# LED_Driver_-_4.net
KiCad netlist of a schematic drawn in Altium Designer
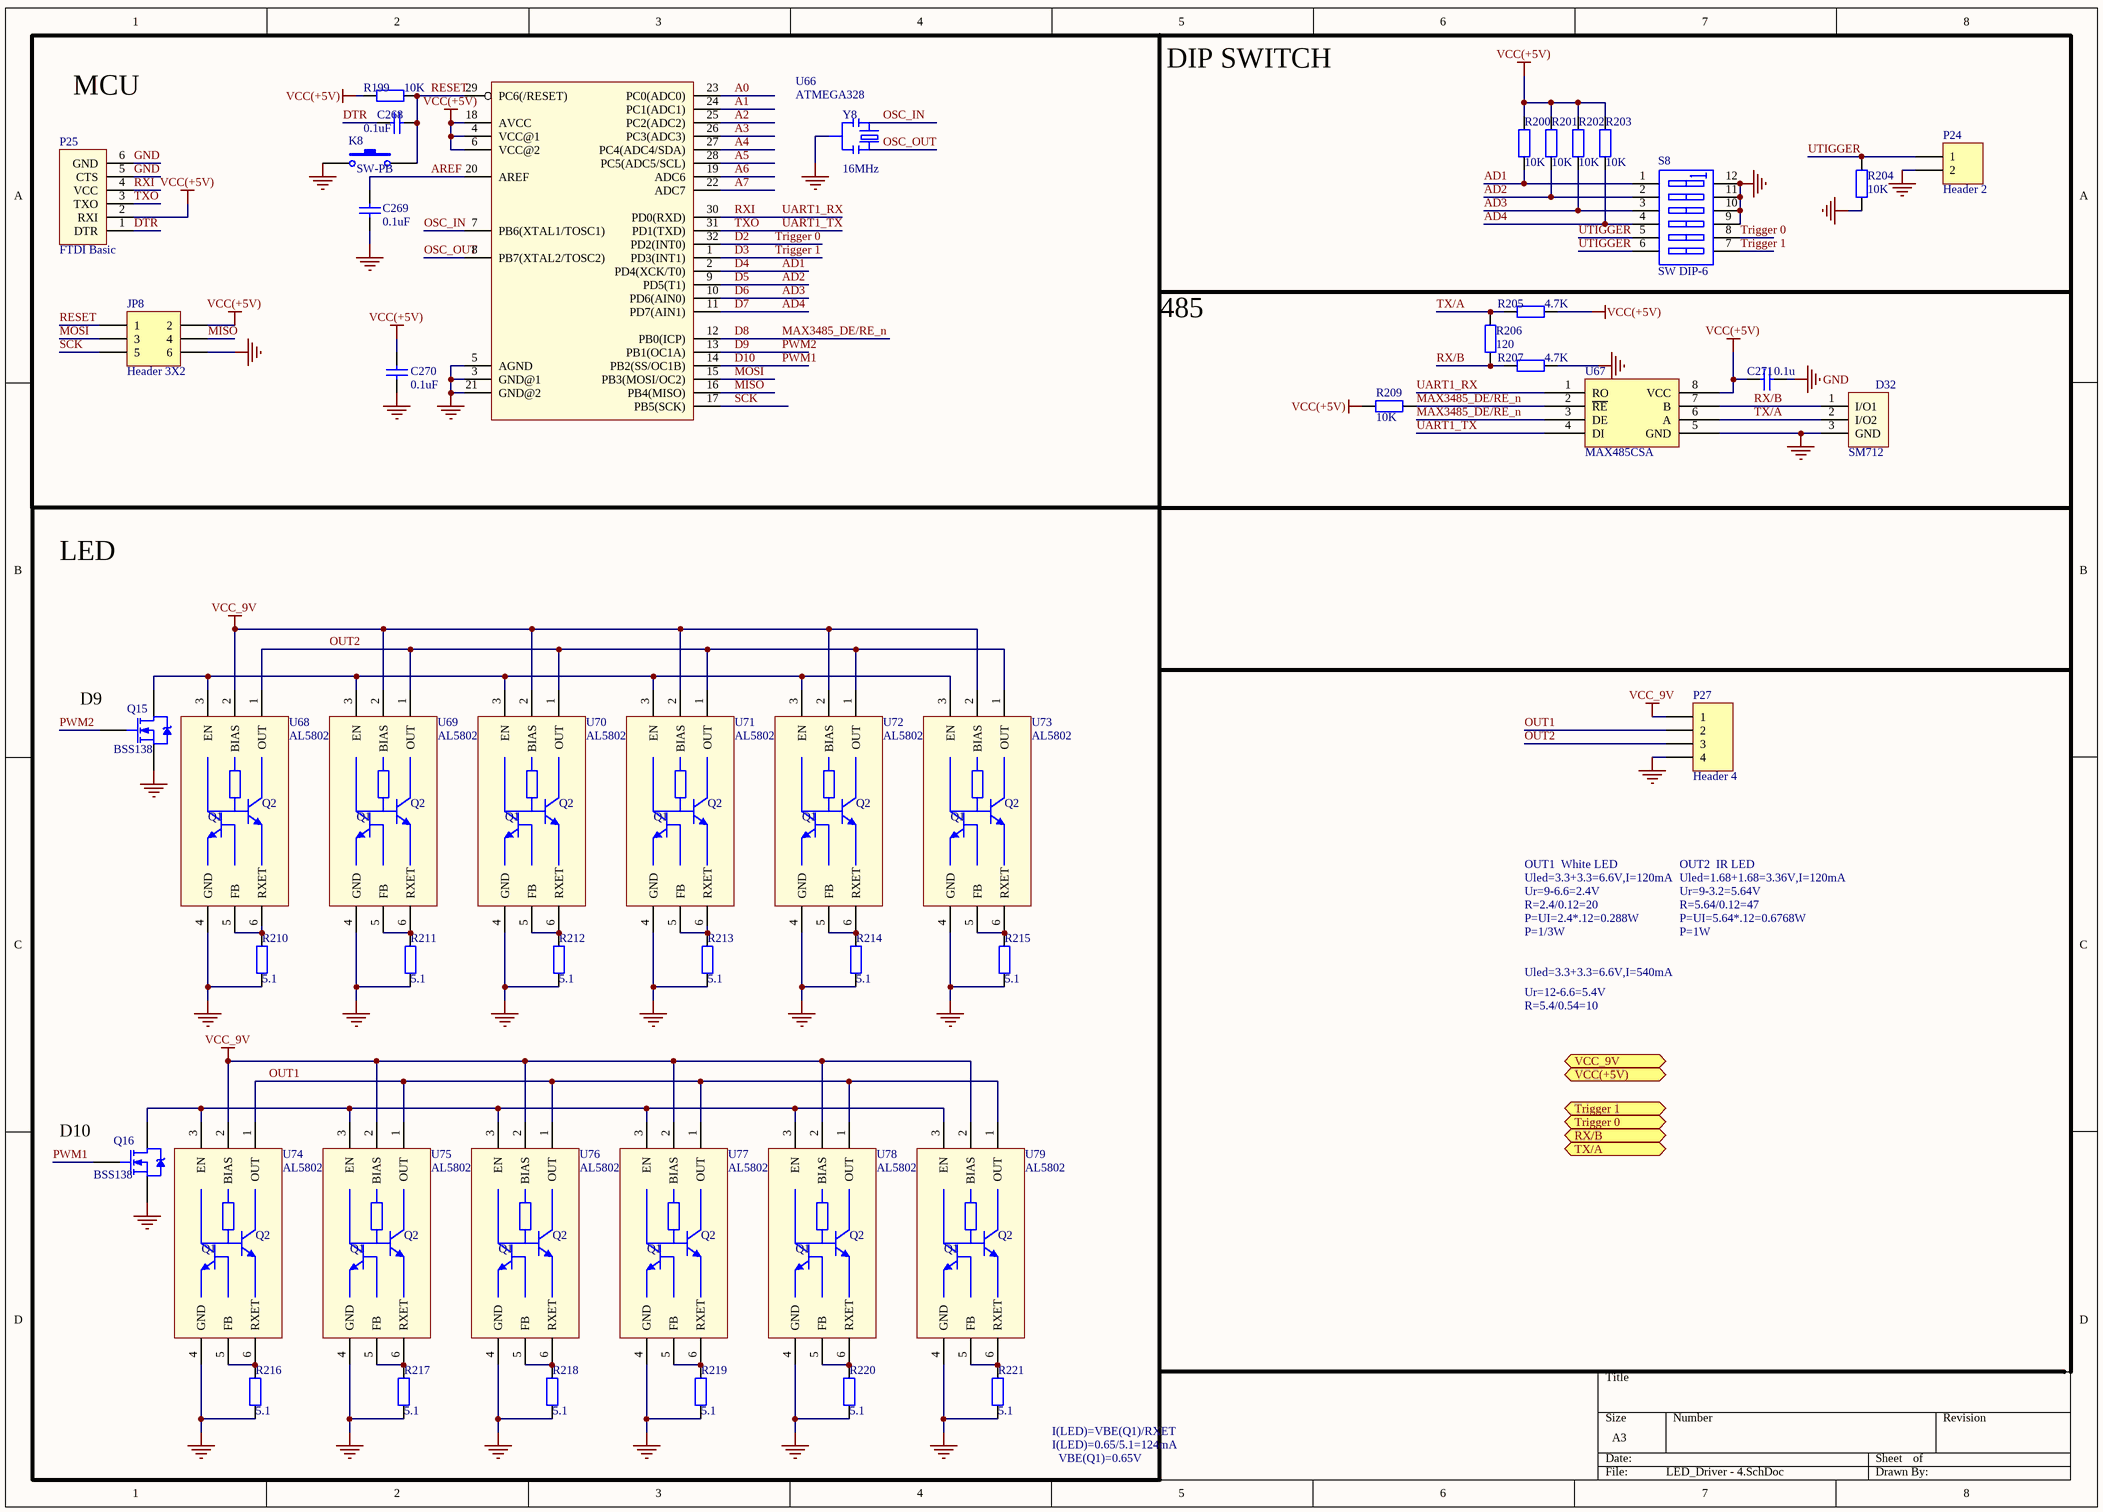
[diagram p0: LED_Driver - 4.SchDoc]

(export (version "E")
  (design (tool "Eeschema 10.0.6"))
  (components
    (comp (ref "C268")
      (value "0.1uF")
      (footprint "C0603")
      (description "Capacitor")
      (fields (field (name "IPARTNUMBER") "C100nF25V10%X7R") (field (name "VOLTAGE") "25V"))
      (libsource (lib "Schlib1") (part "CAP SMT C100nF25V10%X7R"))
    )
    (comp (ref "C269")
      (value "0.1uF")
      (footprint "C0603")
      (description "Capacitor")
      (fields (field (name "IPARTNUMBER") "C100nF25V10%X7R") (field (name "VOLTAGE") "25V"))
      (libsource (lib "Schlib1") (part "CAP SMT C100nF25V10%X7R"))
    )
    (comp (ref "C270")
      (value "0.1uF")
      (footprint "C0603")
      (description "Capacitor")
      (fields (field (name "IPARTNUMBER") "C100nF25V10%X7R") (field (name "VOLTAGE") "25V"))
      (libsource (lib "Schlib1") (part "CAP SMT C100nF25V10%X7R"))
    )
    (comp (ref "C271")
      (value "0.1u")
      (footprint "C0603")
      (description "Capacitor")
      (fields (field (name "PUBLISHER") "Altium Limited"))
      (libsource (lib "Miscellaneous Devices") (part "Cap"))
    )
    (comp (ref "D32")
      (value "SM712")
      (footprint "SOT23-3")
      (libsource (lib "STM32F4_CAM V2.0") (part "SM712"))
    )
    (comp (ref "JP8")
      (value "Header 3X2")
      (footprint "MHDR1X6")
      (description "Header, 3-Pin, Dual row")
      (fields (field (name "PUBLISHER") "Altium Limited"))
      (libsource (lib "Miscellaneous Connectors") (part "Header 3X2"))
    )
    (comp (ref "K8")
      (value "SW-PB")
      (footprint "157SW")
      (description "Switch")
      (fields (field (name "PUBLISHER") "Altium Limited"))
      (libsource (lib "Miscellaneous Devices") (part "SW-PB"))
    )
    (comp (ref "P24")
      (value "Header 2")
      (footprint "HDR1X2")
      (description "Header, 2-Pin")
      (fields (field (name "PUBLISHER") "Altium Limited"))
      (libsource (lib "Miscellaneous Connectors") (part "Header 2"))
    )
    (comp (ref "P25")
      (value "FTDI Basic")
      (footprint "MHDR1X6")
      (libsource (lib "PCB_Project1") (part "ARDUINO_SERIAL_PROGRAMPTH"))
    )
    (comp (ref "P27")
      (value "Header 4")
      (footprint "SMT_1.25MM*4")
      (description "Header, 4-Pin")
      (fields (field (name "PUBLISHER") "Altium Limited"))
      (libsource (lib "Miscellaneous Connectors") (part "Header 4"))
    )
    (comp (ref "Q15")
      (value "BSS138")
      (footprint "SOT-23 (Standard)")
      (fields
        (field (name "MANUFACTURER") "Fairchild Semiconductor")
        (field (name "MANUFACTURER PART NUMBER") "BSS123")
      )
      (libsource (lib "Miscellaneous_Devices") (part "NMOS"))
    )
    (comp (ref "Q16")
      (value "BSS138")
      (footprint "SOT-23 (Standard)")
      (fields
        (field (name "MANUFACTURER") "Fairchild Semiconductor")
        (field (name "MANUFACTURER PART NUMBER") "BSS123")
      )
      (libsource (lib "Miscellaneous_Devices") (part "NMOS"))
    )
    (comp (ref "R199")
      (value "10K")
      (footprint "R0603")
      (description "Resistor")
      (libsource (lib "") (part "Res2_2"))
    )
    (comp (ref "R200")
      (value "10K")
      (footprint "R0603")
      (description "Resistor")
      (libsource (lib "DM642") (part "Res2"))
    )
    (comp (ref "R201")
      (value "10K")
      (footprint "R0603")
      (description "Resistor")
      (libsource (lib "DM642") (part "Res2"))
    )
    (comp (ref "R202")
      (value "10K")
      (footprint "R0603")
      (description "Resistor")
      (libsource (lib "DM642") (part "Res2"))
    )
    (comp (ref "R203")
      (value "10K")
      (footprint "R0603")
      (description "Resistor")
      (libsource (lib "DM642") (part "Res2"))
    )
    (comp (ref "R204")
      (value "10K")
      (footprint "R0603")
      (description "Resistor")
      (fields (field (name "PUBLISHER") "Altium Limited"))
      (libsource (lib "Miscellaneous Devices") (part "Res2"))
    )
    (comp (ref "R205")
      (value "4.7K")
      (footprint "R0603")
      (description "Resistor")
      (libsource (lib "") (part "Res2_1"))
    )
    (comp (ref "R206")
      (value "120")
      (footprint "R0603")
      (description "Resistor")
      (libsource (lib "DM642") (part "Res2"))
    )
    (comp (ref "R207")
      (value "4.7K")
      (footprint "R0603")
      (description "Resistor")
      (libsource (lib "") (part "Res2_1"))
    )
    (comp (ref "R209")
      (value "10K")
      (footprint "R0603")
      (description "Resistor")
      (libsource (lib "") (part "Res2_1"))
    )
    (comp (ref "R210")
      (value "5.1")
      (footprint "R0603")
      (description "Resistor")
      (libsource (lib "DM642") (part "Res2"))
    )
    (comp (ref "R211")
      (value "5.1")
      (footprint "R0603")
      (description "Resistor")
      (libsource (lib "DM642") (part "Res2"))
    )
    (comp (ref "R212")
      (value "5.1")
      (footprint "R0603")
      (description "Resistor")
      (libsource (lib "DM642") (part "Res2"))
    )
    (comp (ref "R213")
      (value "5.1")
      (footprint "R0603")
      (description "Resistor")
      (libsource (lib "DM642") (part "Res2"))
    )
    (comp (ref "R214")
      (value "5.1")
      (footprint "R0603")
      (description "Resistor")
      (libsource (lib "DM642") (part "Res2"))
    )
    (comp (ref "R215")
      (value "5.1")
      (footprint "R0603")
      (description "Resistor")
      (libsource (lib "DM642") (part "Res2"))
    )
    (comp (ref "R216")
      (value "5.1")
      (footprint "R0603")
      (description "Resistor")
      (libsource (lib "DM642") (part "Res2"))
    )
    (comp (ref "R217")
      (value "5.1")
      (footprint "R0603")
      (description "Resistor")
      (libsource (lib "DM642") (part "Res2"))
    )
    (comp (ref "R218")
      (value "5.1")
      (footprint "R0603")
      (description "Resistor")
      (libsource (lib "DM642") (part "Res2"))
    )
    (comp (ref "R219")
      (value "5.1")
      (footprint "R0603")
      (description "Resistor")
      (libsource (lib "DM642") (part "Res2"))
    )
    (comp (ref "R220")
      (value "5.1")
      (footprint "R0603")
      (description "Resistor")
      (libsource (lib "DM642") (part "Res2"))
    )
    (comp (ref "R221")
      (value "5.1")
      (footprint "R0603")
      (description "Resistor")
      (libsource (lib "DM642") (part "Res2"))
    )
    (comp (ref "S8")
      (value "SW DIP-6")
      (footprint "DIP_SW_6WAY_SMD")
      (description "DIP Switch, 6 Position, SPST")
      (fields (field (name "PUBLISHER") "Altium Limited"))
      (libsource (lib "Miscellaneous Devices") (part "SW DIP-6"))
    )
    (comp (ref "U66")
      (value "ATMEGA328")
      (footprint "TQFP32-08")
      (libsource (lib "PCB_Project1") (part "ATMEGA168"))
    )
    (comp (ref "U67")
      (value "MAX485CSA")
      (footprint "SOIC-8")
      (libsource (lib "STM32F4_CAM V1.2") (part "MAX3485CSA"))
    )
    (comp (ref "U68") (value "AL5802") (footprint "SOT26") (libsource (lib "LED") (part "AL5802")))
    (comp (ref "U69") (value "AL5802") (footprint "SOT26") (libsource (lib "LED") (part "AL5802")))
    (comp (ref "U70") (value "AL5802") (footprint "SOT26") (libsource (lib "LED") (part "AL5802")))
    (comp (ref "U71") (value "AL5802") (footprint "SOT26") (libsource (lib "LED") (part "AL5802")))
    (comp (ref "U72") (value "AL5802") (footprint "SOT26") (libsource (lib "LED") (part "AL5802")))
    (comp (ref "U73") (value "AL5802") (footprint "SOT26") (libsource (lib "LED") (part "AL5802")))
    (comp (ref "U74") (value "AL5802") (footprint "SOT26") (libsource (lib "LED") (part "AL5802")))
    (comp (ref "U75") (value "AL5802") (footprint "SOT26") (libsource (lib "LED") (part "AL5802")))
    (comp (ref "U76") (value "AL5802") (footprint "SOT26") (libsource (lib "LED") (part "AL5802")))
    (comp (ref "U77") (value "AL5802") (footprint "SOT26") (libsource (lib "LED") (part "AL5802")))
    (comp (ref "U78") (value "AL5802") (footprint "SOT26") (libsource (lib "LED") (part "AL5802")))
    (comp (ref "U79") (value "AL5802") (footprint "SOT26") (libsource (lib "LED") (part "AL5802")))
    (comp (ref "Y8")
      (value "16MHz")
      (footprint "RESONATOR-SMD")
      (libsource (lib "SparkFun") (part "RESONATORSMD"))
    )
  )
  (nets
    (net (code "1") (name "/A0") (class "Default")
      (node (ref "U66") (pin "23") (pinfunction "PC0(ADC0)_23") (pintype "passive"))
    )
    (net (code "2") (name "/A1") (class "Default")
      (node (ref "U66") (pin "24") (pinfunction "PC1(ADC1)_24") (pintype "passive"))
    )
    (net (code "3") (name "/A2") (class "Default")
      (node (ref "U66") (pin "25") (pinfunction "PC2(ADC2)_25") (pintype "passive"))
    )
    (net (code "4") (name "/A3") (class "Default")
      (node (ref "U66") (pin "26") (pinfunction "PC3(ADC3)_26") (pintype "passive"))
    )
    (net (code "5") (name "/A4") (class "Default")
      (node (ref "U66") (pin "27") (pinfunction "PC4(ADC4/SDA)_27") (pintype "passive"))
    )
    (net (code "6") (name "/A5") (class "Default")
      (node (ref "U66") (pin "28") (pinfunction "PC5(ADC5/SCL)_28") (pintype "passive"))
    )
    (net (code "7") (name "/A6") (class "Default")
      (node (ref "U66") (pin "19") (pinfunction "ADC6_19") (pintype "passive"))
    )
    (net (code "8") (name "/A7") (class "Default")
      (node (ref "U66") (pin "22") (pinfunction "ADC7_22") (pintype "passive"))
    )
    (net (code "9") (name "/AD1") (class "Default")
      (node (ref "R200") (pin "2") (pinfunction "2_2") (pintype "passive"))
      (node (ref "S8") (pin "1") (pinfunction "A1_1") (pintype "passive"))
      (node (ref "U66") (pin "2") (pinfunction "PD4(XCK/T0)_2") (pintype "passive"))
    )
    (net (code "10") (name "/AD2") (class "Default")
      (node (ref "R201") (pin "2") (pinfunction "2_2") (pintype "passive"))
      (node (ref "S8") (pin "2") (pinfunction "A2_2") (pintype "passive"))
      (node (ref "U66") (pin "9") (pinfunction "PD5(T1)_9") (pintype "passive"))
    )
    (net (code "11") (name "/AD3") (class "Default")
      (node (ref "R202") (pin "2") (pinfunction "2_2") (pintype "passive"))
      (node (ref "S8") (pin "3") (pinfunction "A3_3") (pintype "passive"))
      (node (ref "U66") (pin "10") (pinfunction "PD6(AIN0)_10") (pintype "passive"))
    )
    (net (code "12") (name "/AD4") (class "Default")
      (node (ref "R203") (pin "2") (pinfunction "2_2") (pintype "passive"))
      (node (ref "S8") (pin "4") (pinfunction "A4_4") (pintype "passive"))
      (node (ref "U66") (pin "11") (pinfunction "PD7(AIN1)_11") (pintype "passive"))
    )
    (net (code "13") (name "/AREF") (class "Default")
      (node (ref "C269") (pin "2") (pinfunction "2_2") (pintype "passive"))
      (node (ref "U66") (pin "20") (pinfunction "AREF_20") (pintype "passive"))
    )
    (net (code "14") (name "/D2") (class "Default")
      (node (ref "S8") (pin "8") (pinfunction "B5_8") (pintype "passive"))
      (node (ref "U66") (pin "32") (pinfunction "PD2(INT0)_32") (pintype "passive"))
    )
    (net (code "15") (name "/D3") (class "Default")
      (node (ref "S8") (pin "7") (pinfunction "B6_7") (pintype "passive"))
      (node (ref "U66") (pin "1") (pinfunction "PD3(INT1)_1") (pintype "passive"))
    )
    (net (code "16") (name "/D8") (class "Default")
      (node (ref "R209") (pin "1") (pinfunction "1_1") (pintype "passive"))
      (node (ref "U66") (pin "12") (pinfunction "PB0(ICP)_12") (pintype "passive"))
      (node (ref "U67") (pin "2") (pinfunction "~{RE}_2") (pintype "passive"))
      (node (ref "U67") (pin "3") (pinfunction "DE_3") (pintype "passive"))
    )
    (net (code "17") (name "/D9") (class "Default")
      (node (ref "Q15") (pin "G") (pinfunction "G_G") (pintype "passive"))
      (node (ref "U66") (pin "13") (pinfunction "PB1(OC1A)_13") (pintype "passive"))
    )
    (net (code "18") (name "/D10") (class "Default")
      (node (ref "Q16") (pin "G") (pinfunction "G_G") (pintype "passive"))
      (node (ref "U66") (pin "14") (pinfunction "PB2(SS/OC1B)_14") (pintype "passive"))
    )
    (net (code "19") (name "/DTR") (class "Default")
      (node (ref "C268") (pin "1") (pinfunction "1_1") (pintype "passive"))
      (node (ref "P25") (pin "1") (pinfunction "DTR_1") (pintype "passive"))
    )
    (net (code "20") (name "/MISO") (class "Default")
      (node (ref "JP8") (pin "4") (pinfunction "4_4") (pintype "passive"))
      (node (ref "U66") (pin "16") (pinfunction "PB4(MISO)_16") (pintype "passive"))
    )
    (net (code "21") (name "/MOSI") (class "Default")
      (node (ref "JP8") (pin "3") (pinfunction "3_3") (pintype "passive"))
      (node (ref "U66") (pin "15") (pinfunction "PB3(MOSI/OC2)_15") (pintype "passive"))
    )
    (net (code "22") (name "/OSC_IN") (class "Default")
      (node (ref "U66") (pin "7") (pinfunction "PB6(XTAL1/TOSC1)_7") (pintype "passive"))
      (node (ref "Y8") (pin "3") (pinfunction "3_3") (pintype "passive"))
    )
    (net (code "23") (name "/OSC_OUT") (class "Default")
      (node (ref "U66") (pin "8") (pinfunction "PB7(XTAL2/TOSC2)_8") (pintype "passive"))
      (node (ref "Y8") (pin "1") (pinfunction "1_1") (pintype "passive"))
    )
    (net (code "24") (name "/OUT1") (class "Default")
      (node (ref "P27") (pin "2") (pinfunction "2_2") (pintype "passive"))
      (node (ref "U74") (pin "1") (pinfunction "OUT_1") (pintype "passive"))
      (node (ref "U75") (pin "1") (pinfunction "OUT_1") (pintype "passive"))
      (node (ref "U76") (pin "1") (pinfunction "OUT_1") (pintype "passive"))
      (node (ref "U77") (pin "1") (pinfunction "OUT_1") (pintype "passive"))
      (node (ref "U78") (pin "1") (pinfunction "OUT_1") (pintype "passive"))
      (node (ref "U79") (pin "1") (pinfunction "OUT_1") (pintype "passive"))
    )
    (net (code "25") (name "/OUT2") (class "Default")
      (node (ref "P27") (pin "3") (pinfunction "3_3") (pintype "passive"))
      (node (ref "U68") (pin "1") (pinfunction "OUT_1") (pintype "passive"))
      (node (ref "U69") (pin "1") (pinfunction "OUT_1") (pintype "passive"))
      (node (ref "U70") (pin "1") (pinfunction "OUT_1") (pintype "passive"))
      (node (ref "U71") (pin "1") (pinfunction "OUT_1") (pintype "passive"))
      (node (ref "U72") (pin "1") (pinfunction "OUT_1") (pintype "passive"))
      (node (ref "U73") (pin "1") (pinfunction "OUT_1") (pintype "passive"))
    )
    (net (code "26") (name "/RESET") (class "Default")
      (node (ref "C268") (pin "2") (pinfunction "2_2") (pintype "passive"))
      (node (ref "JP8") (pin "1") (pinfunction "1_1") (pintype "passive"))
      (node (ref "K8") (pin "2") (pinfunction "2_2") (pintype "passive"))
      (node (ref "R199") (pin "2") (pinfunction "2_2") (pintype "passive"))
      (node (ref "U66") (pin "29") (pinfunction "PC6(/RESET)_29") (pintype "passive"))
    )
    (net (code "27") (name "/RXI") (class "Default")
      (node (ref "P25") (pin "4") (pinfunction "VCC_4") (pintype "passive"))
      (node (ref "U66") (pin "30") (pinfunction "PD0(RXD)_30") (pintype "passive"))
      (node (ref "U67") (pin "1") (pinfunction "RO_1") (pintype "passive"))
    )
    (net (code "28") (name "/RX{slash}B") (class "Default")
      (node (ref "D32") (pin "1") (pinfunction "I/O1_1") (pintype "passive"))
      (node (ref "R206") (pin "2") (pinfunction "2_2") (pintype "passive"))
      (node (ref "R207") (pin "2") (pinfunction "2_2") (pintype "passive"))
      (node (ref "U67") (pin "7") (pinfunction "B_7") (pintype "passive"))
    )
    (net (code "29") (name "/SCK") (class "Default")
      (node (ref "JP8") (pin "5") (pinfunction "5_5") (pintype "passive"))
      (node (ref "U66") (pin "17") (pinfunction "PB5(SCK)_17") (pintype "passive"))
    )
    (net (code "30") (name "/TXO") (class "Default")
      (node (ref "P25") (pin "3") (pinfunction "TXO_3") (pintype "passive"))
      (node (ref "U66") (pin "31") (pinfunction "PD1(TXD)_31") (pintype "passive"))
      (node (ref "U67") (pin "4") (pinfunction "DI_4") (pintype "passive"))
    )
    (net (code "31") (name "/TX{slash}A") (class "Default")
      (node (ref "D32") (pin "2") (pinfunction "I/O2_2") (pintype "passive"))
      (node (ref "R205") (pin "2") (pinfunction "2_2") (pintype "passive"))
      (node (ref "R206") (pin "1") (pinfunction "1_1") (pintype "passive"))
      (node (ref "U67") (pin "6") (pinfunction "A_6") (pintype "passive"))
    )
    (net (code "32") (name "/UTIGGER") (class "Default")
      (node (ref "P24") (pin "1") (pinfunction "1_1") (pintype "passive"))
      (node (ref "R204") (pin "2") (pinfunction "2_2") (pintype "passive"))
      (node (ref "S8") (pin "5") (pinfunction "A5_5") (pintype "passive"))
      (node (ref "S8") (pin "6") (pinfunction "A6_6") (pintype "passive"))
    )
    (net (code "33") (name "GND") (class "Default")
      (node (ref "C269") (pin "1") (pinfunction "1_1") (pintype "passive"))
      (node (ref "C270") (pin "2") (pinfunction "2_2") (pintype "passive"))
      (node (ref "C271") (pin "1") (pinfunction "1_1") (pintype "passive"))
      (node (ref "D32") (pin "3") (pinfunction "GND_3") (pintype "passive"))
      (node (ref "JP8") (pin "6") (pinfunction "6_6") (pintype "passive"))
      (node (ref "K8") (pin "1") (pinfunction "1_1") (pintype "passive"))
      (node (ref "P24") (pin "2") (pinfunction "2_2") (pintype "passive"))
      (node (ref "P25") (pin "5") (pinfunction "CTS_5") (pintype "passive"))
      (node (ref "P25") (pin "6") (pinfunction "GND_6") (pintype "passive"))
      (node (ref "P27") (pin "4") (pinfunction "4_4") (pintype "passive"))
      (node (ref "Q15") (pin "S") (pinfunction "S_S") (pintype "passive"))
      (node (ref "Q16") (pin "S") (pinfunction "S_S") (pintype "passive"))
      (node (ref "R204") (pin "1") (pinfunction "1_1") (pintype "passive"))
      (node (ref "R207") (pin "1") (pinfunction "1_1") (pintype "passive"))
      (node (ref "R210") (pin "2") (pinfunction "2_2") (pintype "passive"))
      (node (ref "R211") (pin "2") (pinfunction "2_2") (pintype "passive"))
      (node (ref "R212") (pin "2") (pinfunction "2_2") (pintype "passive"))
      (node (ref "R213") (pin "2") (pinfunction "2_2") (pintype "passive"))
      (node (ref "R214") (pin "2") (pinfunction "2_2") (pintype "passive"))
      (node (ref "R215") (pin "2") (pinfunction "2_2") (pintype "passive"))
      (node (ref "R216") (pin "2") (pinfunction "2_2") (pintype "passive"))
      (node (ref "R217") (pin "2") (pinfunction "2_2") (pintype "passive"))
      (node (ref "R218") (pin "2") (pinfunction "2_2") (pintype "passive"))
      (node (ref "R219") (pin "2") (pinfunction "2_2") (pintype "passive"))
      (node (ref "R220") (pin "2") (pinfunction "2_2") (pintype "passive"))
      (node (ref "R221") (pin "2") (pinfunction "2_2") (pintype "passive"))
      (node (ref "S8") (pin "10") (pinfunction "B3_10") (pintype "passive"))
      (node (ref "S8") (pin "11") (pinfunction "B2_11") (pintype "passive"))
      (node (ref "S8") (pin "12") (pinfunction "B1_12") (pintype "passive"))
      (node (ref "S8") (pin "9") (pinfunction "B4_9") (pintype "passive"))
      (node (ref "U66") (pin "21") (pinfunction "GND@2_21") (pintype "passive"))
      (node (ref "U66") (pin "3") (pinfunction "GND@1_3") (pintype "passive"))
      (node (ref "U66") (pin "5") (pinfunction "AGND_5") (pintype "passive"))
      (node (ref "U67") (pin "5") (pinfunction "GND_5") (pintype "passive"))
      (node (ref "U68") (pin "4") (pinfunction "GND_4") (pintype "passive"))
      (node (ref "U69") (pin "4") (pinfunction "GND_4") (pintype "passive"))
      (node (ref "U70") (pin "4") (pinfunction "GND_4") (pintype "passive"))
      (node (ref "U71") (pin "4") (pinfunction "GND_4") (pintype "passive"))
      (node (ref "U72") (pin "4") (pinfunction "GND_4") (pintype "passive"))
      (node (ref "U73") (pin "4") (pinfunction "GND_4") (pintype "passive"))
      (node (ref "U74") (pin "4") (pinfunction "GND_4") (pintype "passive"))
      (node (ref "U75") (pin "4") (pinfunction "GND_4") (pintype "passive"))
      (node (ref "U76") (pin "4") (pinfunction "GND_4") (pintype "passive"))
      (node (ref "U77") (pin "4") (pinfunction "GND_4") (pintype "passive"))
      (node (ref "U78") (pin "4") (pinfunction "GND_4") (pintype "passive"))
      (node (ref "U79") (pin "4") (pinfunction "GND_4") (pintype "passive"))
      (node (ref "Y8") (pin "2") (pinfunction "2_2") (pintype "passive"))
    )
    (net (code "34") (name "Net-(U68-EN)") (class "Default")
      (node (ref "Q15") (pin "D") (pinfunction "D_D") (pintype "passive"))
      (node (ref "U68") (pin "3") (pinfunction "EN_3") (pintype "passive"))
      (node (ref "U69") (pin "3") (pinfunction "EN_3") (pintype "passive"))
      (node (ref "U70") (pin "3") (pinfunction "EN_3") (pintype "passive"))
      (node (ref "U71") (pin "3") (pinfunction "EN_3") (pintype "passive"))
      (node (ref "U72") (pin "3") (pinfunction "EN_3") (pintype "passive"))
      (node (ref "U73") (pin "3") (pinfunction "EN_3") (pintype "passive"))
    )
    (net (code "35") (name "Net-(U68-FB)") (class "Default")
      (node (ref "R210") (pin "1") (pinfunction "1_1") (pintype "passive"))
      (node (ref "U68") (pin "5") (pinfunction "FB_5") (pintype "passive"))
      (node (ref "U68") (pin "6") (pinfunction "RXET_6") (pintype "passive"))
    )
    (net (code "36") (name "Net-(U69-FB)") (class "Default")
      (node (ref "R211") (pin "1") (pinfunction "1_1") (pintype "passive"))
      (node (ref "U69") (pin "5") (pinfunction "FB_5") (pintype "passive"))
      (node (ref "U69") (pin "6") (pinfunction "RXET_6") (pintype "passive"))
    )
    (net (code "37") (name "Net-(U70-FB)") (class "Default")
      (node (ref "R212") (pin "1") (pinfunction "1_1") (pintype "passive"))
      (node (ref "U70") (pin "5") (pinfunction "FB_5") (pintype "passive"))
      (node (ref "U70") (pin "6") (pinfunction "RXET_6") (pintype "passive"))
    )
    (net (code "38") (name "Net-(U71-FB)") (class "Default")
      (node (ref "R213") (pin "1") (pinfunction "1_1") (pintype "passive"))
      (node (ref "U71") (pin "5") (pinfunction "FB_5") (pintype "passive"))
      (node (ref "U71") (pin "6") (pinfunction "RXET_6") (pintype "passive"))
    )
    (net (code "39") (name "Net-(U72-FB)") (class "Default")
      (node (ref "R214") (pin "1") (pinfunction "1_1") (pintype "passive"))
      (node (ref "U72") (pin "5") (pinfunction "FB_5") (pintype "passive"))
      (node (ref "U72") (pin "6") (pinfunction "RXET_6") (pintype "passive"))
    )
    (net (code "40") (name "Net-(U73-FB)") (class "Default")
      (node (ref "R215") (pin "1") (pinfunction "1_1") (pintype "passive"))
      (node (ref "U73") (pin "5") (pinfunction "FB_5") (pintype "passive"))
      (node (ref "U73") (pin "6") (pinfunction "RXET_6") (pintype "passive"))
    )
    (net (code "41") (name "Net-(U74-EN)") (class "Default")
      (node (ref "Q16") (pin "D") (pinfunction "D_D") (pintype "passive"))
      (node (ref "U74") (pin "3") (pinfunction "EN_3") (pintype "passive"))
      (node (ref "U75") (pin "3") (pinfunction "EN_3") (pintype "passive"))
      (node (ref "U76") (pin "3") (pinfunction "EN_3") (pintype "passive"))
      (node (ref "U77") (pin "3") (pinfunction "EN_3") (pintype "passive"))
      (node (ref "U78") (pin "3") (pinfunction "EN_3") (pintype "passive"))
      (node (ref "U79") (pin "3") (pinfunction "EN_3") (pintype "passive"))
    )
    (net (code "42") (name "Net-(U74-FB)") (class "Default")
      (node (ref "R216") (pin "1") (pinfunction "1_1") (pintype "passive"))
      (node (ref "U74") (pin "5") (pinfunction "FB_5") (pintype "passive"))
      (node (ref "U74") (pin "6") (pinfunction "RXET_6") (pintype "passive"))
    )
    (net (code "43") (name "Net-(U75-FB)") (class "Default")
      (node (ref "R217") (pin "1") (pinfunction "1_1") (pintype "passive"))
      (node (ref "U75") (pin "5") (pinfunction "FB_5") (pintype "passive"))
      (node (ref "U75") (pin "6") (pinfunction "RXET_6") (pintype "passive"))
    )
    (net (code "44") (name "Net-(U76-FB)") (class "Default")
      (node (ref "R218") (pin "1") (pinfunction "1_1") (pintype "passive"))
      (node (ref "U76") (pin "5") (pinfunction "FB_5") (pintype "passive"))
      (node (ref "U76") (pin "6") (pinfunction "RXET_6") (pintype "passive"))
    )
    (net (code "45") (name "Net-(U77-FB)") (class "Default")
      (node (ref "R219") (pin "1") (pinfunction "1_1") (pintype "passive"))
      (node (ref "U77") (pin "5") (pinfunction "FB_5") (pintype "passive"))
      (node (ref "U77") (pin "6") (pinfunction "RXET_6") (pintype "passive"))
    )
    (net (code "46") (name "Net-(U78-FB)") (class "Default")
      (node (ref "R220") (pin "1") (pinfunction "1_1") (pintype "passive"))
      (node (ref "U78") (pin "5") (pinfunction "FB_5") (pintype "passive"))
      (node (ref "U78") (pin "6") (pinfunction "RXET_6") (pintype "passive"))
    )
    (net (code "47") (name "Net-(U79-FB)") (class "Default")
      (node (ref "R221") (pin "1") (pinfunction "1_1") (pintype "passive"))
      (node (ref "U79") (pin "5") (pinfunction "FB_5") (pintype "passive"))
      (node (ref "U79") (pin "6") (pinfunction "RXET_6") (pintype "passive"))
    )
    (net (code "48") (name "VCC(+5V)") (class "Default")
      (node (ref "C270") (pin "1") (pinfunction "1_1") (pintype "passive"))
      (node (ref "C271") (pin "2") (pinfunction "2_2") (pintype "passive"))
      (node (ref "JP8") (pin "2") (pinfunction "2_2") (pintype "passive"))
      (node (ref "P25") (pin "2") (pinfunction "RXI_2") (pintype "passive"))
      (node (ref "R199") (pin "1") (pinfunction "1_1") (pintype "passive"))
      (node (ref "R200") (pin "1") (pinfunction "1_1") (pintype "passive"))
      (node (ref "R201") (pin "1") (pinfunction "1_1") (pintype "passive"))
      (node (ref "R202") (pin "1") (pinfunction "1_1") (pintype "passive"))
      (node (ref "R203") (pin "1") (pinfunction "1_1") (pintype "passive"))
      (node (ref "R205") (pin "1") (pinfunction "1_1") (pintype "passive"))
      (node (ref "R209") (pin "2") (pinfunction "2_2") (pintype "passive"))
      (node (ref "U66") (pin "18") (pinfunction "AVCC_18") (pintype "passive"))
      (node (ref "U66") (pin "4") (pinfunction "VCC@1_4") (pintype "passive"))
      (node (ref "U66") (pin "6") (pinfunction "VCC@2_6") (pintype "passive"))
      (node (ref "U67") (pin "8") (pinfunction "VCC_8") (pintype "passive"))
    )
    (net (code "49") (name "VCC_9V") (class "Default")
      (node (ref "P27") (pin "1") (pinfunction "1_1") (pintype "passive"))
      (node (ref "U68") (pin "2") (pinfunction "BIAS_2") (pintype "passive"))
      (node (ref "U69") (pin "2") (pinfunction "BIAS_2") (pintype "passive"))
      (node (ref "U70") (pin "2") (pinfunction "BIAS_2") (pintype "passive"))
      (node (ref "U71") (pin "2") (pinfunction "BIAS_2") (pintype "passive"))
      (node (ref "U72") (pin "2") (pinfunction "BIAS_2") (pintype "passive"))
      (node (ref "U73") (pin "2") (pinfunction "BIAS_2") (pintype "passive"))
      (node (ref "U74") (pin "2") (pinfunction "BIAS_2") (pintype "passive"))
      (node (ref "U75") (pin "2") (pinfunction "BIAS_2") (pintype "passive"))
      (node (ref "U76") (pin "2") (pinfunction "BIAS_2") (pintype "passive"))
      (node (ref "U77") (pin "2") (pinfunction "BIAS_2") (pintype "passive"))
      (node (ref "U78") (pin "2") (pinfunction "BIAS_2") (pintype "passive"))
      (node (ref "U79") (pin "2") (pinfunction "BIAS_2") (pintype "passive"))
    )
  )
)
